# MCU.net
KiCad netlist of a schematic drawn in Altium Designer
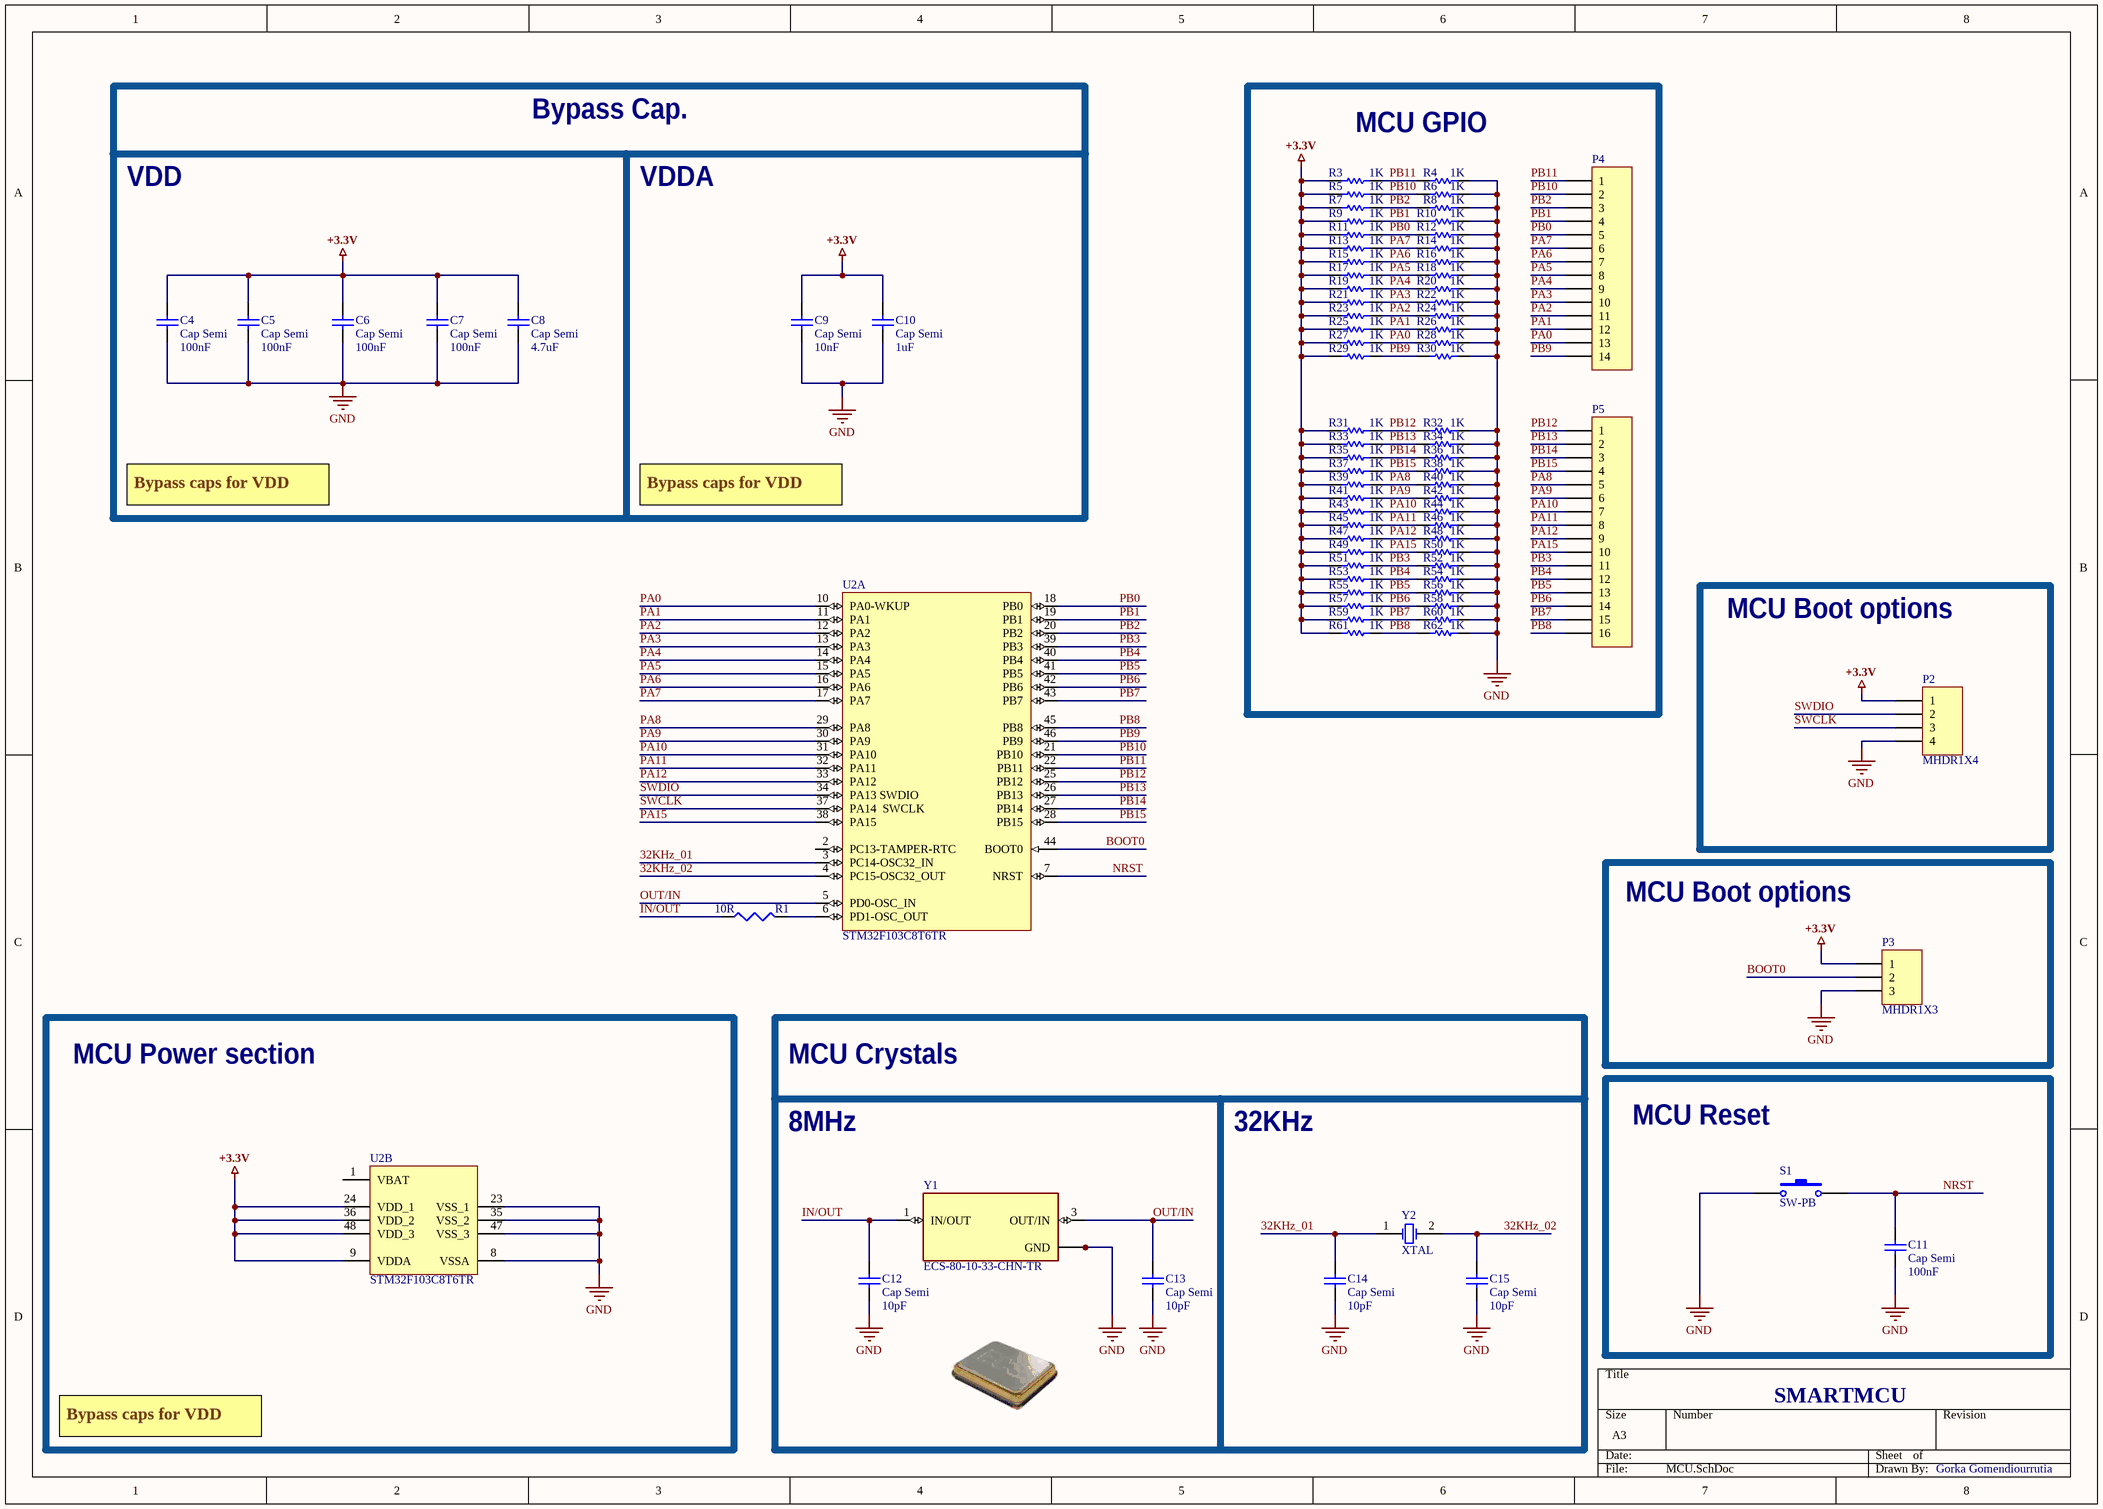
[diagram p0: MCU.SchDoc]

(export (version "E")
  (design (tool "Eeschema 10.0.6"))
  (components
    (comp (ref "C4")
      (value "Cap Semi")
      (footprint "1608[0603]")
      (description "Capacitor (Semiconductor SIM Model)")
      (fields (field (name "ALTIUM_VALUE") "100nF") (field (name "PUBLISHER") "Altium Limited"))
      (libsource (lib "Miscellaneous Devices") (part "Cap Semi"))
    )
    (comp (ref "C5")
      (value "Cap Semi")
      (footprint "1608[0603]")
      (description "Capacitor (Semiconductor SIM Model)")
      (fields (field (name "ALTIUM_VALUE") "100nF") (field (name "PUBLISHER") "Altium Limited"))
      (libsource (lib "Miscellaneous Devices") (part "Cap Semi"))
    )
    (comp (ref "C6")
      (value "Cap Semi")
      (footprint "1608[0603]")
      (description "Capacitor (Semiconductor SIM Model)")
      (fields (field (name "ALTIUM_VALUE") "100nF") (field (name "PUBLISHER") "Altium Limited"))
      (libsource (lib "Miscellaneous Devices") (part "Cap Semi"))
    )
    (comp (ref "C7")
      (value "Cap Semi")
      (footprint "1608[0603]")
      (description "Capacitor (Semiconductor SIM Model)")
      (fields (field (name "ALTIUM_VALUE") "100nF") (field (name "PUBLISHER") "Altium Limited"))
      (libsource (lib "Miscellaneous Devices") (part "Cap Semi"))
    )
    (comp (ref "C8")
      (value "Cap Semi")
      (footprint "1608[0603]")
      (description "Capacitor (Semiconductor SIM Model)")
      (fields (field (name "ALTIUM_VALUE") "4.7uF") (field (name "PUBLISHER") "Altium Limited"))
      (libsource (lib "Miscellaneous Devices") (part "Cap Semi"))
    )
    (comp (ref "C9")
      (value "Cap Semi")
      (footprint "1608[0603]")
      (description "Capacitor (Semiconductor SIM Model)")
      (fields (field (name "ALTIUM_VALUE") "10nF") (field (name "PUBLISHER") "Altium Limited"))
      (libsource (lib "Miscellaneous Devices") (part "Cap Semi"))
    )
    (comp (ref "C10")
      (value "Cap Semi")
      (footprint "1608[0603]")
      (description "Capacitor (Semiconductor SIM Model)")
      (fields (field (name "ALTIUM_VALUE") "1uF") (field (name "PUBLISHER") "Altium Limited"))
      (libsource (lib "Miscellaneous Devices") (part "Cap Semi"))
    )
    (comp (ref "C11")
      (value "Cap Semi")
      (footprint "1608[0603]")
      (description "Capacitor (Semiconductor SIM Model)")
      (fields (field (name "ALTIUM_VALUE") "100nF") (field (name "PUBLISHER") "Altium Limited"))
      (libsource (lib "Miscellaneous Devices") (part "Cap Semi"))
    )
    (comp (ref "C12")
      (value "Cap Semi")
      (footprint "0402")
      (description "Capacitor (Semiconductor SIM Model)")
      (fields (field (name "ALTIUM_VALUE") "10pF") (field (name "PUBLISHER") "Altium Limited"))
      (libsource (lib "Miscellaneous Devices") (part "Cap Semi"))
    )
    (comp (ref "C13")
      (value "Cap Semi")
      (footprint "0402")
      (description "Capacitor (Semiconductor SIM Model)")
      (fields (field (name "ALTIUM_VALUE") "10pF") (field (name "PUBLISHER") "Altium Limited"))
      (libsource (lib "Miscellaneous Devices") (part "Cap Semi"))
    )
    (comp (ref "C14")
      (value "Cap Semi")
      (footprint "0402")
      (description "Capacitor (Semiconductor SIM Model)")
      (fields (field (name "ALTIUM_VALUE") "10pF") (field (name "PUBLISHER") "Altium Limited"))
      (libsource (lib "Miscellaneous Devices") (part "Cap Semi"))
    )
    (comp (ref "C15")
      (value "Cap Semi")
      (footprint "0402")
      (description "Capacitor (Semiconductor SIM Model)")
      (fields (field (name "ALTIUM_VALUE") "10pF") (field (name "PUBLISHER") "Altium Limited"))
      (libsource (lib "Miscellaneous Devices") (part "Cap Semi"))
    )
    (comp (ref "P2")
      (value "MHDR1X4")
      (footprint "MHDR1X4")
      (description "Header, 4-Pin")
      (fields (field (name "PUBLISHER") "Altium Limited"))
      (libsource (lib "Miscellaneous Connectors") (part "MHDR1X4"))
    )
    (comp (ref "P3")
      (value "MHDR1X3")
      (footprint "MHDR1X3")
      (description "Header, 3-Pin")
      (fields (field (name "PUBLISHER") "Altium Limited"))
      (libsource (lib "Miscellaneous Connectors") (part "MHDR1X3"))
    )
    (comp (ref "P4")
      (value "Header 14")
      (footprint "MY_FE14")
      (description "Header, 14-Pin")
      (fields (field (name "ASID PART NUMBER") "Header 14-AS"))
      (libsource (lib "Mylib+Rev+4") (part "Header 14"))
    )
    (comp (ref "P5")
      (value "Header 16")
      (footprint "MY_FE16")
      (description "Header, 16-Pin")
      (fields (field (name "ASID PART NUMBER") "Header 16-AS"))
      (libsource (lib "Mylib+Rev+4") (part "Header 16"))
    )
    (comp (ref "R1")
      (value "10R")
      (footprint "J1-0603")
      (description "Resistor")
      (fields (field (name "Comment") "Res3") (field (name "PUBLISHER") "Altium Limited"))
      (libsource (lib "Miscellaneous Devices") (part "Res3"))
    )
    (comp (ref "R3")
      (value "1K")
      (footprint "MY_0603")
      (description "Standard resistor")
      (fields (field (name "ASID PART NUMBER") "Res-AS"))
      (libsource (lib "Mylib+Rev+4") (part "Res"))
    )
    (comp (ref "R4")
      (value "1K")
      (footprint "MY_0603")
      (description "Standard resistor")
      (fields (field (name "ASID PART NUMBER") "Res-AS"))
      (libsource (lib "Mylib+Rev+4") (part "Res"))
    )
    (comp (ref "R5")
      (value "1K")
      (footprint "MY_0603")
      (description "Standard resistor")
      (fields (field (name "ASID PART NUMBER") "Res-AS"))
      (libsource (lib "Mylib+Rev+4") (part "Res"))
    )
    (comp (ref "R6")
      (value "1K")
      (footprint "MY_0603")
      (description "Standard resistor")
      (fields (field (name "ASID PART NUMBER") "Res-AS"))
      (libsource (lib "Mylib+Rev+4") (part "Res"))
    )
    (comp (ref "R7")
      (value "1K")
      (footprint "MY_0603")
      (description "Standard resistor")
      (fields (field (name "ASID PART NUMBER") "Res-AS"))
      (libsource (lib "Mylib+Rev+4") (part "Res"))
    )
    (comp (ref "R8")
      (value "1K")
      (footprint "MY_0603")
      (description "Standard resistor")
      (fields (field (name "ASID PART NUMBER") "Res-AS"))
      (libsource (lib "Mylib+Rev+4") (part "Res"))
    )
    (comp (ref "R9")
      (value "1K")
      (footprint "MY_0603")
      (description "Standard resistor")
      (fields (field (name "ASID PART NUMBER") "Res-AS"))
      (libsource (lib "Mylib+Rev+4") (part "Res"))
    )
    (comp (ref "R10")
      (value "1K")
      (footprint "MY_0603")
      (description "Standard resistor")
      (fields (field (name "ASID PART NUMBER") "Res-AS"))
      (libsource (lib "Mylib+Rev+4") (part "Res"))
    )
    (comp (ref "R11")
      (value "1K")
      (footprint "MY_0603")
      (description "Standard resistor")
      (fields (field (name "ASID PART NUMBER") "Res-AS"))
      (libsource (lib "Mylib+Rev+4") (part "Res"))
    )
    (comp (ref "R12")
      (value "1K")
      (footprint "MY_0603")
      (description "Standard resistor")
      (fields (field (name "ASID PART NUMBER") "Res-AS"))
      (libsource (lib "Mylib+Rev+4") (part "Res"))
    )
    (comp (ref "R13")
      (value "1K")
      (footprint "MY_0603")
      (description "Standard resistor")
      (fields (field (name "ASID PART NUMBER") "Res-AS"))
      (libsource (lib "Mylib+Rev+4") (part "Res"))
    )
    (comp (ref "R14")
      (value "1K")
      (footprint "MY_0603")
      (description "Standard resistor")
      (fields (field (name "ASID PART NUMBER") "Res-AS"))
      (libsource (lib "Mylib+Rev+4") (part "Res"))
    )
    (comp (ref "R15")
      (value "1K")
      (footprint "MY_0603")
      (description "Standard resistor")
      (fields (field (name "ASID PART NUMBER") "Res-AS"))
      (libsource (lib "Mylib+Rev+4") (part "Res"))
    )
    (comp (ref "R16")
      (value "1K")
      (footprint "MY_0603")
      (description "Standard resistor")
      (fields (field (name "ASID PART NUMBER") "Res-AS"))
      (libsource (lib "Mylib+Rev+4") (part "Res"))
    )
    (comp (ref "R17")
      (value "1K")
      (footprint "MY_0603")
      (description "Standard resistor")
      (fields (field (name "ASID PART NUMBER") "Res-AS"))
      (libsource (lib "Mylib+Rev+4") (part "Res"))
    )
    (comp (ref "R18")
      (value "1K")
      (footprint "MY_0603")
      (description "Standard resistor")
      (fields (field (name "ASID PART NUMBER") "Res-AS"))
      (libsource (lib "Mylib+Rev+4") (part "Res"))
    )
    (comp (ref "R19")
      (value "1K")
      (footprint "MY_0603")
      (description "Standard resistor")
      (fields (field (name "ASID PART NUMBER") "Res-AS"))
      (libsource (lib "Mylib+Rev+4") (part "Res"))
    )
    (comp (ref "R20")
      (value "1K")
      (footprint "MY_0603")
      (description "Standard resistor")
      (fields (field (name "ASID PART NUMBER") "Res-AS"))
      (libsource (lib "Mylib+Rev+4") (part "Res"))
    )
    (comp (ref "R21")
      (value "1K")
      (footprint "MY_0603")
      (description "Standard resistor")
      (fields (field (name "ASID PART NUMBER") "Res-AS"))
      (libsource (lib "Mylib+Rev+4") (part "Res"))
    )
    (comp (ref "R22")
      (value "1K")
      (footprint "MY_0603")
      (description "Standard resistor")
      (fields (field (name "ASID PART NUMBER") "Res-AS"))
      (libsource (lib "Mylib+Rev+4") (part "Res"))
    )
    (comp (ref "R23")
      (value "1K")
      (footprint "MY_0603")
      (description "Standard resistor")
      (fields (field (name "ASID PART NUMBER") "Res-AS"))
      (libsource (lib "Mylib+Rev+4") (part "Res"))
    )
    (comp (ref "R24")
      (value "1K")
      (footprint "MY_0603")
      (description "Standard resistor")
      (fields (field (name "ASID PART NUMBER") "Res-AS"))
      (libsource (lib "Mylib+Rev+4") (part "Res"))
    )
    (comp (ref "R25")
      (value "1K")
      (footprint "MY_0603")
      (description "Standard resistor")
      (fields (field (name "ASID PART NUMBER") "Res-AS"))
      (libsource (lib "Mylib+Rev+4") (part "Res"))
    )
    (comp (ref "R26")
      (value "1K")
      (footprint "MY_0603")
      (description "Standard resistor")
      (fields (field (name "ASID PART NUMBER") "Res-AS"))
      (libsource (lib "Mylib+Rev+4") (part "Res"))
    )
    (comp (ref "R27")
      (value "1K")
      (footprint "MY_0603")
      (description "Standard resistor")
      (fields (field (name "ASID PART NUMBER") "Res-AS"))
      (libsource (lib "Mylib+Rev+4") (part "Res"))
    )
    (comp (ref "R28")
      (value "1K")
      (footprint "MY_0603")
      (description "Standard resistor")
      (fields (field (name "ASID PART NUMBER") "Res-AS"))
      (libsource (lib "Mylib+Rev+4") (part "Res"))
    )
    (comp (ref "R29")
      (value "1K")
      (footprint "MY_0603")
      (description "Standard resistor")
      (fields (field (name "ASID PART NUMBER") "Res-AS"))
      (libsource (lib "Mylib+Rev+4") (part "Res"))
    )
    (comp (ref "R30")
      (value "1K")
      (footprint "MY_0603")
      (description "Standard resistor")
      (fields (field (name "ASID PART NUMBER") "Res-AS"))
      (libsource (lib "Mylib+Rev+4") (part "Res"))
    )
    (comp (ref "R31")
      (value "1K")
      (footprint "MY_0603")
      (description "Standard resistor")
      (fields (field (name "ASID PART NUMBER") "Res-AS"))
      (libsource (lib "Mylib+Rev+4") (part "Res"))
    )
    (comp (ref "R32")
      (value "1K")
      (footprint "MY_0603")
      (description "Standard resistor")
      (fields (field (name "ASID PART NUMBER") "Res-AS"))
      (libsource (lib "Mylib+Rev+4") (part "Res"))
    )
    (comp (ref "R33")
      (value "1K")
      (footprint "MY_0603")
      (description "Standard resistor")
      (fields (field (name "ASID PART NUMBER") "Res-AS"))
      (libsource (lib "Mylib+Rev+4") (part "Res"))
    )
    (comp (ref "R34")
      (value "1K")
      (footprint "MY_0603")
      (description "Standard resistor")
      (fields (field (name "ASID PART NUMBER") "Res-AS"))
      (libsource (lib "Mylib+Rev+4") (part "Res"))
    )
    (comp (ref "R35")
      (value "1K")
      (footprint "MY_0603")
      (description "Standard resistor")
      (fields (field (name "ASID PART NUMBER") "Res-AS"))
      (libsource (lib "Mylib+Rev+4") (part "Res"))
    )
    (comp (ref "R36")
      (value "1K")
      (footprint "MY_0603")
      (description "Standard resistor")
      (fields (field (name "ASID PART NUMBER") "Res-AS"))
      (libsource (lib "Mylib+Rev+4") (part "Res"))
    )
    (comp (ref "R37")
      (value "1K")
      (footprint "MY_0603")
      (description "Standard resistor")
      (fields (field (name "ASID PART NUMBER") "Res-AS"))
      (libsource (lib "Mylib+Rev+4") (part "Res"))
    )
    (comp (ref "R38")
      (value "1K")
      (footprint "MY_0603")
      (description "Standard resistor")
      (fields (field (name "ASID PART NUMBER") "Res-AS"))
      (libsource (lib "Mylib+Rev+4") (part "Res"))
    )
    (comp (ref "R39")
      (value "1K")
      (footprint "MY_0603")
      (description "Standard resistor")
      (fields (field (name "ASID PART NUMBER") "Res-AS"))
      (libsource (lib "Mylib+Rev+4") (part "Res"))
    )
    (comp (ref "R40")
      (value "1K")
      (footprint "MY_0603")
      (description "Standard resistor")
      (fields (field (name "ASID PART NUMBER") "Res-AS"))
      (libsource (lib "Mylib+Rev+4") (part "Res"))
    )
    (comp (ref "R41")
      (value "1K")
      (footprint "MY_0603")
      (description "Standard resistor")
      (fields (field (name "ASID PART NUMBER") "Res-AS"))
      (libsource (lib "Mylib+Rev+4") (part "Res"))
    )
    (comp (ref "R42")
      (value "1K")
      (footprint "MY_0603")
      (description "Standard resistor")
      (fields (field (name "ASID PART NUMBER") "Res-AS"))
      (libsource (lib "Mylib+Rev+4") (part "Res"))
    )
    (comp (ref "R43")
      (value "1K")
      (footprint "MY_0603")
      (description "Standard resistor")
      (fields (field (name "ASID PART NUMBER") "Res-AS"))
      (libsource (lib "Mylib+Rev+4") (part "Res"))
    )
    (comp (ref "R44")
      (value "1K")
      (footprint "MY_0603")
      (description "Standard resistor")
      (fields (field (name "ASID PART NUMBER") "Res-AS"))
      (libsource (lib "Mylib+Rev+4") (part "Res"))
    )
    (comp (ref "R45")
      (value "1K")
      (footprint "MY_0603")
      (description "Standard resistor")
      (fields (field (name "ASID PART NUMBER") "Res-AS"))
      (libsource (lib "Mylib+Rev+4") (part "Res"))
    )
    (comp (ref "R46")
      (value "1K")
      (footprint "MY_0603")
      (description "Standard resistor")
      (fields (field (name "ASID PART NUMBER") "Res-AS"))
      (libsource (lib "Mylib+Rev+4") (part "Res"))
    )
    (comp (ref "R47")
      (value "1K")
      (footprint "MY_0603")
      (description "Standard resistor")
      (fields (field (name "ASID PART NUMBER") "Res-AS"))
      (libsource (lib "Mylib+Rev+4") (part "Res"))
    )
    (comp (ref "R48")
      (value "1K")
      (footprint "MY_0603")
      (description "Standard resistor")
      (fields (field (name "ASID PART NUMBER") "Res-AS"))
      (libsource (lib "Mylib+Rev+4") (part "Res"))
    )
    (comp (ref "R49")
      (value "1K")
      (footprint "MY_0603")
      (description "Standard resistor")
      (fields (field (name "ASID PART NUMBER") "Res-AS"))
      (libsource (lib "Mylib+Rev+4") (part "Res"))
    )
    (comp (ref "R50")
      (value "1K")
      (footprint "MY_0603")
      (description "Standard resistor")
      (fields (field (name "ASID PART NUMBER") "Res-AS"))
      (libsource (lib "Mylib+Rev+4") (part "Res"))
    )
    (comp (ref "R51")
      (value "1K")
      (footprint "MY_0603")
      (description "Standard resistor")
      (fields (field (name "ASID PART NUMBER") "Res-AS"))
      (libsource (lib "Mylib+Rev+4") (part "Res"))
    )
    (comp (ref "R52")
      (value "1K")
      (footprint "MY_0603")
      (description "Standard resistor")
      (fields (field (name "ASID PART NUMBER") "Res-AS"))
      (libsource (lib "Mylib+Rev+4") (part "Res"))
    )
    (comp (ref "R53")
      (value "1K")
      (footprint "MY_0603")
      (description "Standard resistor")
      (fields (field (name "ASID PART NUMBER") "Res-AS"))
      (libsource (lib "Mylib+Rev+4") (part "Res"))
    )
    (comp (ref "R54")
      (value "1K")
      (footprint "MY_0603")
      (description "Standard resistor")
      (fields (field (name "ASID PART NUMBER") "Res-AS"))
      (libsource (lib "Mylib+Rev+4") (part "Res"))
    )
    (comp (ref "R55")
      (value "1K")
      (footprint "MY_0603")
      (description "Standard resistor")
      (fields (field (name "ASID PART NUMBER") "Res-AS"))
      (libsource (lib "Mylib+Rev+4") (part "Res"))
    )
    (comp (ref "R56")
      (value "1K")
      (footprint "MY_0603")
      (description "Standard resistor")
      (fields (field (name "ASID PART NUMBER") "Res-AS"))
      (libsource (lib "Mylib+Rev+4") (part "Res"))
    )
    (comp (ref "R57")
      (value "1K")
      (footprint "MY_0603")
      (description "Standard resistor")
      (fields (field (name "ASID PART NUMBER") "Res-AS"))
      (libsource (lib "Mylib+Rev+4") (part "Res"))
    )
    (comp (ref "R58")
      (value "1K")
      (footprint "MY_0603")
      (description "Standard resistor")
      (fields (field (name "ASID PART NUMBER") "Res-AS"))
      (libsource (lib "Mylib+Rev+4") (part "Res"))
    )
    (comp (ref "R59")
      (value "1K")
      (footprint "MY_0603")
      (description "Standard resistor")
      (fields (field (name "ASID PART NUMBER") "Res-AS"))
      (libsource (lib "Mylib+Rev+4") (part "Res"))
    )
    (comp (ref "R60")
      (value "1K")
      (footprint "MY_0603")
      (description "Standard resistor")
      (fields (field (name "ASID PART NUMBER") "Res-AS"))
      (libsource (lib "Mylib+Rev+4") (part "Res"))
    )
    (comp (ref "R61")
      (value "1K")
      (footprint "MY_0603")
      (description "Standard resistor")
      (fields (field (name "ASID PART NUMBER") "Res-AS"))
      (libsource (lib "Mylib+Rev+4") (part "Res"))
    )
    (comp (ref "R62")
      (value "1K")
      (footprint "MY_0603")
      (description "Standard resistor")
      (fields (field (name "ASID PART NUMBER") "Res-AS"))
      (libsource (lib "Mylib+Rev+4") (part "Res"))
    )
    (comp (ref "S1")
      (value "SW-PB")
      (footprint "SPST-2")
      (description "Switch")
      (fields (field (name "PUBLISHER") "Altium Limited"))
      (libsource (lib "Miscellaneous Devices") (part "SW-PB"))
    )
    (comp (ref "U2")
      (value "STM32F103C8T6TR")
      (footprint "STM-LQFP48_N")
      (libsource (lib "STMicroelectronics STM32 F1") (part "STM32F103C8T6TR"))
    )
    (comp (ref "Y1")
      (value "ECS-80-10-33-CHN-TR")
      (footprint "XTAL_ECS-80-10-33-CHN-TR")
      (description "8 MHz Â±10ppm Crystal 10pF 400 Ohms 4-SMD, No Lead")
      (fields (field (name "MF") "ECS Inc."))
      (libsource (lib "ECS-80-10-33-CHN-TR") (part "ECS-80-10-33-CHN-TR"))
    )
    (comp (ref "Y2")
      (value "XTAL")
      (footprint "R38")
      (description "Crystal Oscillator")
      (fields (field (name "PUBLISHER") "Altium Limited"))
      (libsource (lib "Miscellaneous Devices") (part "XTAL"))
    )
  )
  (nets
    (net (code "1") (name "+3.3V") (class "Default")
      (node (ref "C10") (pin "2") (pinfunction "2_2") (pintype "passive"))
      (node (ref "C4") (pin "2") (pinfunction "2_2") (pintype "passive"))
      (node (ref "C5") (pin "2") (pinfunction "2_2") (pintype "passive"))
      (node (ref "C6") (pin "2") (pinfunction "2_2") (pintype "passive"))
      (node (ref "C7") (pin "2") (pinfunction "2_2") (pintype "passive"))
      (node (ref "C8") (pin "2") (pinfunction "2_2") (pintype "passive"))
      (node (ref "C9") (pin "2") (pinfunction "2_2") (pintype "passive"))
      (node (ref "P2") (pin "1") (pinfunction "1_1") (pintype "passive"))
      (node (ref "P3") (pin "1") (pinfunction "1_1") (pintype "passive"))
      (node (ref "R11") (pin "1") (pinfunction "1_1") (pintype "passive"))
      (node (ref "R13") (pin "1") (pinfunction "1_1") (pintype "passive"))
      (node (ref "R15") (pin "1") (pinfunction "1_1") (pintype "passive"))
      (node (ref "R17") (pin "1") (pinfunction "1_1") (pintype "passive"))
      (node (ref "R19") (pin "1") (pinfunction "1_1") (pintype "passive"))
      (node (ref "R21") (pin "1") (pinfunction "1_1") (pintype "passive"))
      (node (ref "R23") (pin "1") (pinfunction "1_1") (pintype "passive"))
      (node (ref "R25") (pin "1") (pinfunction "1_1") (pintype "passive"))
      (node (ref "R27") (pin "1") (pinfunction "1_1") (pintype "passive"))
      (node (ref "R29") (pin "1") (pinfunction "1_1") (pintype "passive"))
      (node (ref "R3") (pin "1") (pinfunction "1_1") (pintype "passive"))
      (node (ref "R31") (pin "1") (pinfunction "1_1") (pintype "passive"))
      (node (ref "R33") (pin "1") (pinfunction "1_1") (pintype "passive"))
      (node (ref "R35") (pin "1") (pinfunction "1_1") (pintype "passive"))
      (node (ref "R37") (pin "1") (pinfunction "1_1") (pintype "passive"))
      (node (ref "R39") (pin "1") (pinfunction "1_1") (pintype "passive"))
      (node (ref "R41") (pin "1") (pinfunction "1_1") (pintype "passive"))
      (node (ref "R43") (pin "1") (pinfunction "1_1") (pintype "passive"))
      (node (ref "R45") (pin "1") (pinfunction "1_1") (pintype "passive"))
      (node (ref "R47") (pin "1") (pinfunction "1_1") (pintype "passive"))
      (node (ref "R49") (pin "1") (pinfunction "1_1") (pintype "passive"))
      (node (ref "R5") (pin "1") (pinfunction "1_1") (pintype "passive"))
      (node (ref "R51") (pin "1") (pinfunction "1_1") (pintype "passive"))
      (node (ref "R53") (pin "1") (pinfunction "1_1") (pintype "passive"))
      (node (ref "R55") (pin "1") (pinfunction "1_1") (pintype "passive"))
      (node (ref "R57") (pin "1") (pinfunction "1_1") (pintype "passive"))
      (node (ref "R59") (pin "1") (pinfunction "1_1") (pintype "passive"))
      (node (ref "R61") (pin "1") (pinfunction "1_1") (pintype "passive"))
      (node (ref "R7") (pin "1") (pinfunction "1_1") (pintype "passive"))
      (node (ref "R9") (pin "1") (pinfunction "1_1") (pintype "passive"))
      (node (ref "U2") (pin "24") (pinfunction "VDD_1_24") (pintype "power_in"))
      (node (ref "U2") (pin "36") (pinfunction "VDD_2_36") (pintype "power_in"))
      (node (ref "U2") (pin "48") (pinfunction "VDD_3_48") (pintype "power_in"))
      (node (ref "U2") (pin "9") (pinfunction "VDDA_9") (pintype "power_in"))
    )
    (net (code "2") (name "/32KHz_01") (class "Default")
      (node (ref "C14") (pin "2") (pinfunction "2_2") (pintype "passive"))
      (node (ref "U2") (pin "3") (pinfunction "PC14-OSC32_IN_3") (pintype "bidirectional"))
      (node (ref "Y2") (pin "1") (pinfunction "OSC1_1") (pintype "passive"))
    )
    (net (code "3") (name "/32KHz_02") (class "Default")
      (node (ref "C15") (pin "2") (pinfunction "2_2") (pintype "passive"))
      (node (ref "U2") (pin "4") (pinfunction "PC15-OSC32_OUT_4") (pintype "bidirectional"))
      (node (ref "Y2") (pin "2") (pinfunction "OSC2_2") (pintype "passive"))
    )
    (net (code "4") (name "/BOOT0") (class "Default")
      (node (ref "P3") (pin "2") (pinfunction "2_2") (pintype "passive"))
      (node (ref "U2") (pin "44") (pinfunction "BOOT0_44") (pintype "input"))
    )
    (net (code "5") (name "/IN{slash}OUT") (class "Default")
      (node (ref "C12") (pin "2") (pinfunction "2_2") (pintype "passive"))
      (node (ref "R1") (pin "1") (pinfunction "1_1") (pintype "passive"))
      (node (ref "Y1") (pin "1") (pinfunction "IN/OUT_1") (pintype "bidirectional"))
    )
    (net (code "6") (name "/NRST") (class "Default")
      (node (ref "C11") (pin "2") (pinfunction "2_2") (pintype "passive"))
      (node (ref "S1") (pin "2") (pinfunction "2_2") (pintype "passive"))
      (node (ref "U2") (pin "7") (pinfunction "NRST_7") (pintype "bidirectional"))
    )
    (net (code "7") (name "/OUT{slash}IN") (class "Default")
      (node (ref "C13") (pin "2") (pinfunction "2_2") (pintype "passive"))
      (node (ref "U2") (pin "5") (pinfunction "PD0-OSC_IN_5") (pintype "bidirectional"))
      (node (ref "Y1") (pin "3") (pinfunction "OUT/IN_3") (pintype "bidirectional"))
    )
    (net (code "8") (name "/PA0") (class "Default")
      (node (ref "P4") (pin "13") (pinfunction "13_13") (pintype "passive"))
      (node (ref "R27") (pin "2") (pinfunction "2_2") (pintype "passive"))
      (node (ref "R28") (pin "1") (pinfunction "1_1") (pintype "passive"))
      (node (ref "U2") (pin "10") (pinfunction "PA0-WKUP_10") (pintype "bidirectional"))
    )
    (net (code "9") (name "/PA1") (class "Default")
      (node (ref "P4") (pin "12") (pinfunction "12_12") (pintype "passive"))
      (node (ref "R25") (pin "2") (pinfunction "2_2") (pintype "passive"))
      (node (ref "R26") (pin "1") (pinfunction "1_1") (pintype "passive"))
      (node (ref "U2") (pin "11") (pinfunction "PA1_11") (pintype "bidirectional"))
    )
    (net (code "10") (name "/PA2") (class "Default")
      (node (ref "P4") (pin "11") (pinfunction "11_11") (pintype "passive"))
      (node (ref "R23") (pin "2") (pinfunction "2_2") (pintype "passive"))
      (node (ref "R24") (pin "1") (pinfunction "1_1") (pintype "passive"))
      (node (ref "U2") (pin "12") (pinfunction "PA2_12") (pintype "bidirectional"))
    )
    (net (code "11") (name "/PA3") (class "Default")
      (node (ref "P4") (pin "10") (pinfunction "10_10") (pintype "passive"))
      (node (ref "R21") (pin "2") (pinfunction "2_2") (pintype "passive"))
      (node (ref "R22") (pin "1") (pinfunction "1_1") (pintype "passive"))
      (node (ref "U2") (pin "13") (pinfunction "PA3_13") (pintype "bidirectional"))
    )
    (net (code "12") (name "/PA4") (class "Default")
      (node (ref "P4") (pin "9") (pinfunction "9_9") (pintype "passive"))
      (node (ref "R19") (pin "2") (pinfunction "2_2") (pintype "passive"))
      (node (ref "R20") (pin "1") (pinfunction "1_1") (pintype "passive"))
      (node (ref "U2") (pin "14") (pinfunction "PA4_14") (pintype "bidirectional"))
    )
    (net (code "13") (name "/PA5") (class "Default")
      (node (ref "P4") (pin "8") (pinfunction "8_8") (pintype "passive"))
      (node (ref "R17") (pin "2") (pinfunction "2_2") (pintype "passive"))
      (node (ref "R18") (pin "1") (pinfunction "1_1") (pintype "passive"))
      (node (ref "U2") (pin "15") (pinfunction "PA5_15") (pintype "bidirectional"))
    )
    (net (code "14") (name "/PA6") (class "Default")
      (node (ref "P4") (pin "7") (pinfunction "7_7") (pintype "passive"))
      (node (ref "R15") (pin "2") (pinfunction "2_2") (pintype "passive"))
      (node (ref "R16") (pin "1") (pinfunction "1_1") (pintype "passive"))
      (node (ref "U2") (pin "16") (pinfunction "PA6_16") (pintype "bidirectional"))
    )
    (net (code "15") (name "/PA7") (class "Default")
      (node (ref "P4") (pin "6") (pinfunction "6_6") (pintype "passive"))
      (node (ref "R13") (pin "2") (pinfunction "2_2") (pintype "passive"))
      (node (ref "R14") (pin "1") (pinfunction "1_1") (pintype "passive"))
      (node (ref "U2") (pin "17") (pinfunction "PA7_17") (pintype "bidirectional"))
    )
    (net (code "16") (name "/PA8") (class "Default")
      (node (ref "P5") (pin "5") (pinfunction "5_5") (pintype "passive"))
      (node (ref "R39") (pin "2") (pinfunction "2_2") (pintype "passive"))
      (node (ref "R40") (pin "1") (pinfunction "1_1") (pintype "passive"))
      (node (ref "U2") (pin "29") (pinfunction "PA8_29") (pintype "bidirectional"))
    )
    (net (code "17") (name "/PA9") (class "Default")
      (node (ref "P5") (pin "6") (pinfunction "6_6") (pintype "passive"))
      (node (ref "R41") (pin "2") (pinfunction "2_2") (pintype "passive"))
      (node (ref "R42") (pin "1") (pinfunction "1_1") (pintype "passive"))
      (node (ref "U2") (pin "30") (pinfunction "PA9_30") (pintype "bidirectional"))
    )
    (net (code "18") (name "/PA10") (class "Default")
      (node (ref "P5") (pin "7") (pinfunction "7_7") (pintype "passive"))
      (node (ref "R43") (pin "2") (pinfunction "2_2") (pintype "passive"))
      (node (ref "R44") (pin "1") (pinfunction "1_1") (pintype "passive"))
      (node (ref "U2") (pin "31") (pinfunction "PA10_31") (pintype "bidirectional"))
    )
    (net (code "19") (name "/PA11") (class "Default")
      (node (ref "P5") (pin "8") (pinfunction "8_8") (pintype "passive"))
      (node (ref "R45") (pin "2") (pinfunction "2_2") (pintype "passive"))
      (node (ref "R46") (pin "1") (pinfunction "1_1") (pintype "passive"))
      (node (ref "U2") (pin "32") (pinfunction "PA11_32") (pintype "bidirectional"))
    )
    (net (code "20") (name "/PA12") (class "Default")
      (node (ref "P5") (pin "9") (pinfunction "9_9") (pintype "passive"))
      (node (ref "R47") (pin "2") (pinfunction "2_2") (pintype "passive"))
      (node (ref "R48") (pin "1") (pinfunction "1_1") (pintype "passive"))
      (node (ref "U2") (pin "33") (pinfunction "PA12_33") (pintype "bidirectional"))
    )
    (net (code "21") (name "/PA15") (class "Default")
      (node (ref "P5") (pin "10") (pinfunction "10_10") (pintype "passive"))
      (node (ref "R49") (pin "2") (pinfunction "2_2") (pintype "passive"))
      (node (ref "R50") (pin "1") (pinfunction "1_1") (pintype "passive"))
      (node (ref "U2") (pin "38") (pinfunction "PA15_38") (pintype "bidirectional"))
    )
    (net (code "22") (name "/PB0") (class "Default")
      (node (ref "P4") (pin "5") (pinfunction "5_5") (pintype "passive"))
      (node (ref "R11") (pin "2") (pinfunction "2_2") (pintype "passive"))
      (node (ref "R12") (pin "1") (pinfunction "1_1") (pintype "passive"))
      (node (ref "U2") (pin "18") (pinfunction "PB0_18") (pintype "bidirectional"))
    )
    (net (code "23") (name "/PB1") (class "Default")
      (node (ref "P4") (pin "4") (pinfunction "4_4") (pintype "passive"))
      (node (ref "R10") (pin "1") (pinfunction "1_1") (pintype "passive"))
      (node (ref "R9") (pin "2") (pinfunction "2_2") (pintype "passive"))
      (node (ref "U2") (pin "19") (pinfunction "PB1_19") (pintype "bidirectional"))
    )
    (net (code "24") (name "/PB2") (class "Default")
      (node (ref "P4") (pin "3") (pinfunction "3_3") (pintype "passive"))
      (node (ref "R7") (pin "2") (pinfunction "2_2") (pintype "passive"))
      (node (ref "R8") (pin "1") (pinfunction "1_1") (pintype "passive"))
      (node (ref "U2") (pin "20") (pinfunction "PB2_20") (pintype "bidirectional"))
    )
    (net (code "25") (name "/PB3") (class "Default")
      (node (ref "P5") (pin "11") (pinfunction "11_11") (pintype "passive"))
      (node (ref "R51") (pin "2") (pinfunction "2_2") (pintype "passive"))
      (node (ref "R52") (pin "1") (pinfunction "1_1") (pintype "passive"))
      (node (ref "U2") (pin "39") (pinfunction "PB3_39") (pintype "bidirectional"))
    )
    (net (code "26") (name "/PB4") (class "Default")
      (node (ref "P5") (pin "12") (pinfunction "12_12") (pintype "passive"))
      (node (ref "R53") (pin "2") (pinfunction "2_2") (pintype "passive"))
      (node (ref "R54") (pin "1") (pinfunction "1_1") (pintype "passive"))
      (node (ref "U2") (pin "40") (pinfunction "PB4_40") (pintype "bidirectional"))
    )
    (net (code "27") (name "/PB5") (class "Default")
      (node (ref "P5") (pin "13") (pinfunction "13_13") (pintype "passive"))
      (node (ref "R55") (pin "2") (pinfunction "2_2") (pintype "passive"))
      (node (ref "R56") (pin "1") (pinfunction "1_1") (pintype "passive"))
      (node (ref "U2") (pin "41") (pinfunction "PB5_41") (pintype "bidirectional"))
    )
    (net (code "28") (name "/PB6") (class "Default")
      (node (ref "P5") (pin "14") (pinfunction "14_14") (pintype "passive"))
      (node (ref "R57") (pin "2") (pinfunction "2_2") (pintype "passive"))
      (node (ref "R58") (pin "1") (pinfunction "1_1") (pintype "passive"))
      (node (ref "U2") (pin "42") (pinfunction "PB6_42") (pintype "bidirectional"))
    )
    (net (code "29") (name "/PB7") (class "Default")
      (node (ref "P5") (pin "15") (pinfunction "15_15") (pintype "passive"))
      (node (ref "R59") (pin "2") (pinfunction "2_2") (pintype "passive"))
      (node (ref "R60") (pin "1") (pinfunction "1_1") (pintype "passive"))
      (node (ref "U2") (pin "43") (pinfunction "PB7_43") (pintype "bidirectional"))
    )
    (net (code "30") (name "/PB8") (class "Default")
      (node (ref "P5") (pin "16") (pinfunction "16_16") (pintype "passive"))
      (node (ref "R61") (pin "2") (pinfunction "2_2") (pintype "passive"))
      (node (ref "R62") (pin "1") (pinfunction "1_1") (pintype "passive"))
      (node (ref "U2") (pin "45") (pinfunction "PB8_45") (pintype "bidirectional"))
    )
    (net (code "31") (name "/PB9") (class "Default")
      (node (ref "P4") (pin "14") (pinfunction "14_14") (pintype "passive"))
      (node (ref "R29") (pin "2") (pinfunction "2_2") (pintype "passive"))
      (node (ref "R30") (pin "1") (pinfunction "1_1") (pintype "passive"))
      (node (ref "U2") (pin "46") (pinfunction "PB9_46") (pintype "bidirectional"))
    )
    (net (code "32") (name "/PB10") (class "Default")
      (node (ref "P4") (pin "2") (pinfunction "2_2") (pintype "passive"))
      (node (ref "R5") (pin "2") (pinfunction "2_2") (pintype "passive"))
      (node (ref "R6") (pin "1") (pinfunction "1_1") (pintype "passive"))
      (node (ref "U2") (pin "21") (pinfunction "PB10_21") (pintype "bidirectional"))
    )
    (net (code "33") (name "/PB11") (class "Default")
      (node (ref "P4") (pin "1") (pinfunction "1_1") (pintype "passive"))
      (node (ref "R3") (pin "2") (pinfunction "2_2") (pintype "passive"))
      (node (ref "R4") (pin "1") (pinfunction "1_1") (pintype "passive"))
      (node (ref "U2") (pin "22") (pinfunction "PB11_22") (pintype "bidirectional"))
    )
    (net (code "34") (name "/PB12") (class "Default")
      (node (ref "P5") (pin "1") (pinfunction "1_1") (pintype "passive"))
      (node (ref "R31") (pin "2") (pinfunction "2_2") (pintype "passive"))
      (node (ref "R32") (pin "1") (pinfunction "1_1") (pintype "passive"))
      (node (ref "U2") (pin "25") (pinfunction "PB12_25") (pintype "bidirectional"))
    )
    (net (code "35") (name "/PB13") (class "Default")
      (node (ref "P5") (pin "2") (pinfunction "2_2") (pintype "passive"))
      (node (ref "R33") (pin "2") (pinfunction "2_2") (pintype "passive"))
      (node (ref "R34") (pin "1") (pinfunction "1_1") (pintype "passive"))
      (node (ref "U2") (pin "26") (pinfunction "PB13_26") (pintype "bidirectional"))
    )
    (net (code "36") (name "/PB14") (class "Default")
      (node (ref "P5") (pin "3") (pinfunction "3_3") (pintype "passive"))
      (node (ref "R35") (pin "2") (pinfunction "2_2") (pintype "passive"))
      (node (ref "R36") (pin "1") (pinfunction "1_1") (pintype "passive"))
      (node (ref "U2") (pin "27") (pinfunction "PB14_27") (pintype "bidirectional"))
    )
    (net (code "37") (name "/PB15") (class "Default")
      (node (ref "P5") (pin "4") (pinfunction "4_4") (pintype "passive"))
      (node (ref "R37") (pin "2") (pinfunction "2_2") (pintype "passive"))
      (node (ref "R38") (pin "1") (pinfunction "1_1") (pintype "passive"))
      (node (ref "U2") (pin "28") (pinfunction "PB15_28") (pintype "bidirectional"))
    )
    (net (code "38") (name "/SWCLK") (class "Default")
      (node (ref "P2") (pin "3") (pinfunction "3_3") (pintype "passive"))
      (node (ref "U2") (pin "37") (pinfunction "PA14__SWCLK_37") (pintype "bidirectional"))
    )
    (net (code "39") (name "/SWDIO") (class "Default")
      (node (ref "P2") (pin "2") (pinfunction "2_2") (pintype "passive"))
      (node (ref "U2") (pin "34") (pinfunction "PA13_SWDIO_34") (pintype "bidirectional"))
    )
    (net (code "40") (name "GND") (class "Default")
      (node (ref "C10") (pin "1") (pinfunction "1_1") (pintype "passive"))
      (node (ref "C11") (pin "1") (pinfunction "1_1") (pintype "passive"))
      (node (ref "C12") (pin "1") (pinfunction "1_1") (pintype "passive"))
      (node (ref "C13") (pin "1") (pinfunction "1_1") (pintype "passive"))
      (node (ref "C14") (pin "1") (pinfunction "1_1") (pintype "passive"))
      (node (ref "C15") (pin "1") (pinfunction "1_1") (pintype "passive"))
      (node (ref "C4") (pin "1") (pinfunction "1_1") (pintype "passive"))
      (node (ref "C5") (pin "1") (pinfunction "1_1") (pintype "passive"))
      (node (ref "C6") (pin "1") (pinfunction "1_1") (pintype "passive"))
      (node (ref "C7") (pin "1") (pinfunction "1_1") (pintype "passive"))
      (node (ref "C8") (pin "1") (pinfunction "1_1") (pintype "passive"))
      (node (ref "C9") (pin "1") (pinfunction "1_1") (pintype "passive"))
      (node (ref "P2") (pin "4") (pinfunction "4_4") (pintype "passive"))
      (node (ref "P3") (pin "3") (pinfunction "3_3") (pintype "passive"))
      (node (ref "R10") (pin "2") (pinfunction "2_2") (pintype "passive"))
      (node (ref "R12") (pin "2") (pinfunction "2_2") (pintype "passive"))
      (node (ref "R14") (pin "2") (pinfunction "2_2") (pintype "passive"))
      (node (ref "R16") (pin "2") (pinfunction "2_2") (pintype "passive"))
      (node (ref "R18") (pin "2") (pinfunction "2_2") (pintype "passive"))
      (node (ref "R20") (pin "2") (pinfunction "2_2") (pintype "passive"))
      (node (ref "R22") (pin "2") (pinfunction "2_2") (pintype "passive"))
      (node (ref "R24") (pin "2") (pinfunction "2_2") (pintype "passive"))
      (node (ref "R26") (pin "2") (pinfunction "2_2") (pintype "passive"))
      (node (ref "R28") (pin "2") (pinfunction "2_2") (pintype "passive"))
      (node (ref "R30") (pin "2") (pinfunction "2_2") (pintype "passive"))
      (node (ref "R32") (pin "2") (pinfunction "2_2") (pintype "passive"))
      (node (ref "R34") (pin "2") (pinfunction "2_2") (pintype "passive"))
      (node (ref "R36") (pin "2") (pinfunction "2_2") (pintype "passive"))
      (node (ref "R38") (pin "2") (pinfunction "2_2") (pintype "passive"))
      (node (ref "R4") (pin "2") (pinfunction "2_2") (pintype "passive"))
      (node (ref "R40") (pin "2") (pinfunction "2_2") (pintype "passive"))
      (node (ref "R42") (pin "2") (pinfunction "2_2") (pintype "passive"))
      (node (ref "R44") (pin "2") (pinfunction "2_2") (pintype "passive"))
      (node (ref "R46") (pin "2") (pinfunction "2_2") (pintype "passive"))
      (node (ref "R48") (pin "2") (pinfunction "2_2") (pintype "passive"))
      (node (ref "R50") (pin "2") (pinfunction "2_2") (pintype "passive"))
      (node (ref "R52") (pin "2") (pinfunction "2_2") (pintype "passive"))
      (node (ref "R54") (pin "2") (pinfunction "2_2") (pintype "passive"))
      (node (ref "R56") (pin "2") (pinfunction "2_2") (pintype "passive"))
      (node (ref "R58") (pin "2") (pinfunction "2_2") (pintype "passive"))
      (node (ref "R6") (pin "2") (pinfunction "2_2") (pintype "passive"))
      (node (ref "R60") (pin "2") (pinfunction "2_2") (pintype "passive"))
      (node (ref "R62") (pin "2") (pinfunction "2_2") (pintype "passive"))
      (node (ref "R8") (pin "2") (pinfunction "2_2") (pintype "passive"))
      (node (ref "S1") (pin "1") (pinfunction "1_1") (pintype "passive"))
      (node (ref "U2") (pin "23") (pinfunction "VSS_1_23") (pintype "power_in"))
      (node (ref "U2") (pin "35") (pinfunction "VSS_2_35") (pintype "power_in"))
      (node (ref "U2") (pin "47") (pinfunction "VSS_3_47") (pintype "power_in"))
      (node (ref "U2") (pin "8") (pinfunction "VSSA_8") (pintype "power_in"))
      (node (ref "Y1") (pin "2") (pinfunction "GND_2") (pintype "power_in"))
      (node (ref "Y1") (pin "4") (pinfunction "GND_4") (pintype "power_in"))
    )
    (net (code "41") (name "Net-(U2A-PD1-OSC_OUT)") (class "Default")
      (node (ref "R1") (pin "2") (pinfunction "2_2") (pintype "passive"))
      (node (ref "U2") (pin "6") (pinfunction "PD1-OSC_OUT_6") (pintype "bidirectional"))
    )
    (net (code "42") (name "unconnected-(U2A-PC13-TAMPER-RTC-Pad2)") (class "Default")
      (node (ref "U2") (pin "2") (pinfunction "PC13-TAMPER-RTC_2") (pintype "bidirectional"))
    )
    (net (code "43") (name "unconnected-(U2B-VBAT-Pad1)") (class "Default")
      (node (ref "U2") (pin "1") (pinfunction "VBAT_1") (pintype "power_in"))
    )
  )
)
